# STM32-PROX_8.net
KiCad netlist of a schematic drawn in Altium Designer
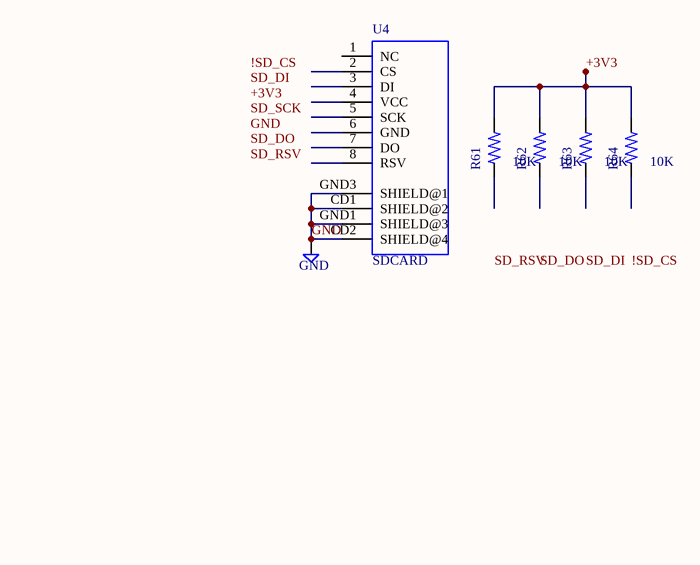
[diagram p0: STM32-PROX_8.SchDoc]

(export (version "E")
  (design (tool "Eeschema 10.0.6"))
  (components
    (comp (ref "GND22") (value "GND") (libsource (lib "STM32-PROX") (part "GND")))
    (comp (ref "R61")
      (value "10K")
      (footprint "RLC_0603")
      (libsource (lib "STM32-PROX") (part "RESISTORRLC_0603"))
    )
    (comp (ref "R62")
      (value "10K")
      (footprint "RLC_0603")
      (libsource (lib "STM32-PROX") (part "RESISTORRLC_0603"))
    )
    (comp (ref "R63")
      (value "10K")
      (footprint "RLC_0603")
      (libsource (lib "STM32-PROX") (part "RESISTORRLC_0603"))
    )
    (comp (ref "R64")
      (value "10K")
      (footprint "RLC_0603")
      (libsource (lib "STM32-PROX") (part "RESISTORRLC_0603"))
    )
    (comp (ref "U4")
      (value "SDCARD")
      (footprint "MICRO-SD-SOCKET-PP")
      (libsource (lib "STM32-PROX") (part "USD-SOCKETNEW"))
    )
  )
  (nets
    (net (code "2") (name "/+3V3") (class "Default")
      (node (ref "R61") (pin "2") (pinfunction "2_2") (pintype "passive"))
      (node (ref "R62") (pin "2") (pinfunction "2_2") (pintype "passive"))
      (node (ref "R63") (pin "2") (pinfunction "2_2") (pintype "passive"))
      (node (ref "R64") (pin "2") (pinfunction "2_2") (pintype "passive"))
    )
    (net (code "3") (name "/GND") (class "Default")
      (node (ref "GND22") (pin "0") (pinfunction "GND_0") (pintype "passive"))
      (node (ref "U4") (pin "CD1") (pinfunction "SHIELD@2_CD1") (pintype "passive"))
      (node (ref "U4") (pin "CD2") (pinfunction "SHIELD@4_CD2") (pintype "passive"))
      (node (ref "U4") (pin "GND1") (pinfunction "SHIELD@3_GND1") (pintype "passive"))
      (node (ref "U4") (pin "GND3") (pinfunction "SHIELD@1_GND3") (pintype "passive"))
    )
    (net (code "8") (name "unconnected-(R61-Pad1)") (class "Default")
      (node (ref "R61") (pin "1") (pinfunction "1_1") (pintype "passive"))
    )
    (net (code "9") (name "unconnected-(R62-Pad1)") (class "Default")
      (node (ref "R62") (pin "1") (pinfunction "1_1") (pintype "passive"))
    )
    (net (code "10") (name "unconnected-(R63-Pad1)") (class "Default")
      (node (ref "R63") (pin "1") (pinfunction "1_1") (pintype "passive"))
    )
    (net (code "11") (name "unconnected-(R64-Pad1)") (class "Default")
      (node (ref "R64") (pin "1") (pinfunction "1_1") (pintype "passive"))
    )
    (net (code "12") (name "unconnected-(U4-CS-Pad2)") (class "Default")
      (node (ref "U4") (pin "2") (pinfunction "CS_2") (pintype "passive"))
    )
    (net (code "13") (name "unconnected-(U4-DI-Pad3)") (class "Default")
      (node (ref "U4") (pin "3") (pinfunction "DI_3") (pintype "passive"))
    )
    (net (code "14") (name "unconnected-(U4-DO-Pad7)") (class "Default")
      (node (ref "U4") (pin "7") (pinfunction "DO_7") (pintype "passive"))
    )
    (net (code "15") (name "unconnected-(U4-GND-Pad6)") (class "Default")
      (node (ref "U4") (pin "6") (pinfunction "GND_6") (pintype "passive"))
    )
    (net (code "16") (name "unconnected-(U4-NC-Pad1)") (class "Default")
      (node (ref "U4") (pin "1") (pinfunction "NC_1") (pintype "passive"))
    )
    (net (code "17") (name "unconnected-(U4-RSV-Pad8)") (class "Default")
      (node (ref "U4") (pin "8") (pinfunction "RSV_8") (pintype "passive"))
    )
    (net (code "18") (name "unconnected-(U4-SCK-Pad5)") (class "Default")
      (node (ref "U4") (pin "5") (pinfunction "SCK_5") (pintype "passive"))
    )
    (net (code "19") (name "unconnected-(U4-VCC-Pad4)") (class "Default")
      (node (ref "U4") (pin "4") (pinfunction "VCC_4") (pintype "passive"))
    )
  )
)
